# ProPrj_USB_Hub_2026-06-01.net
KiCad netlist of a schematic drawn in EasyEDA Pro
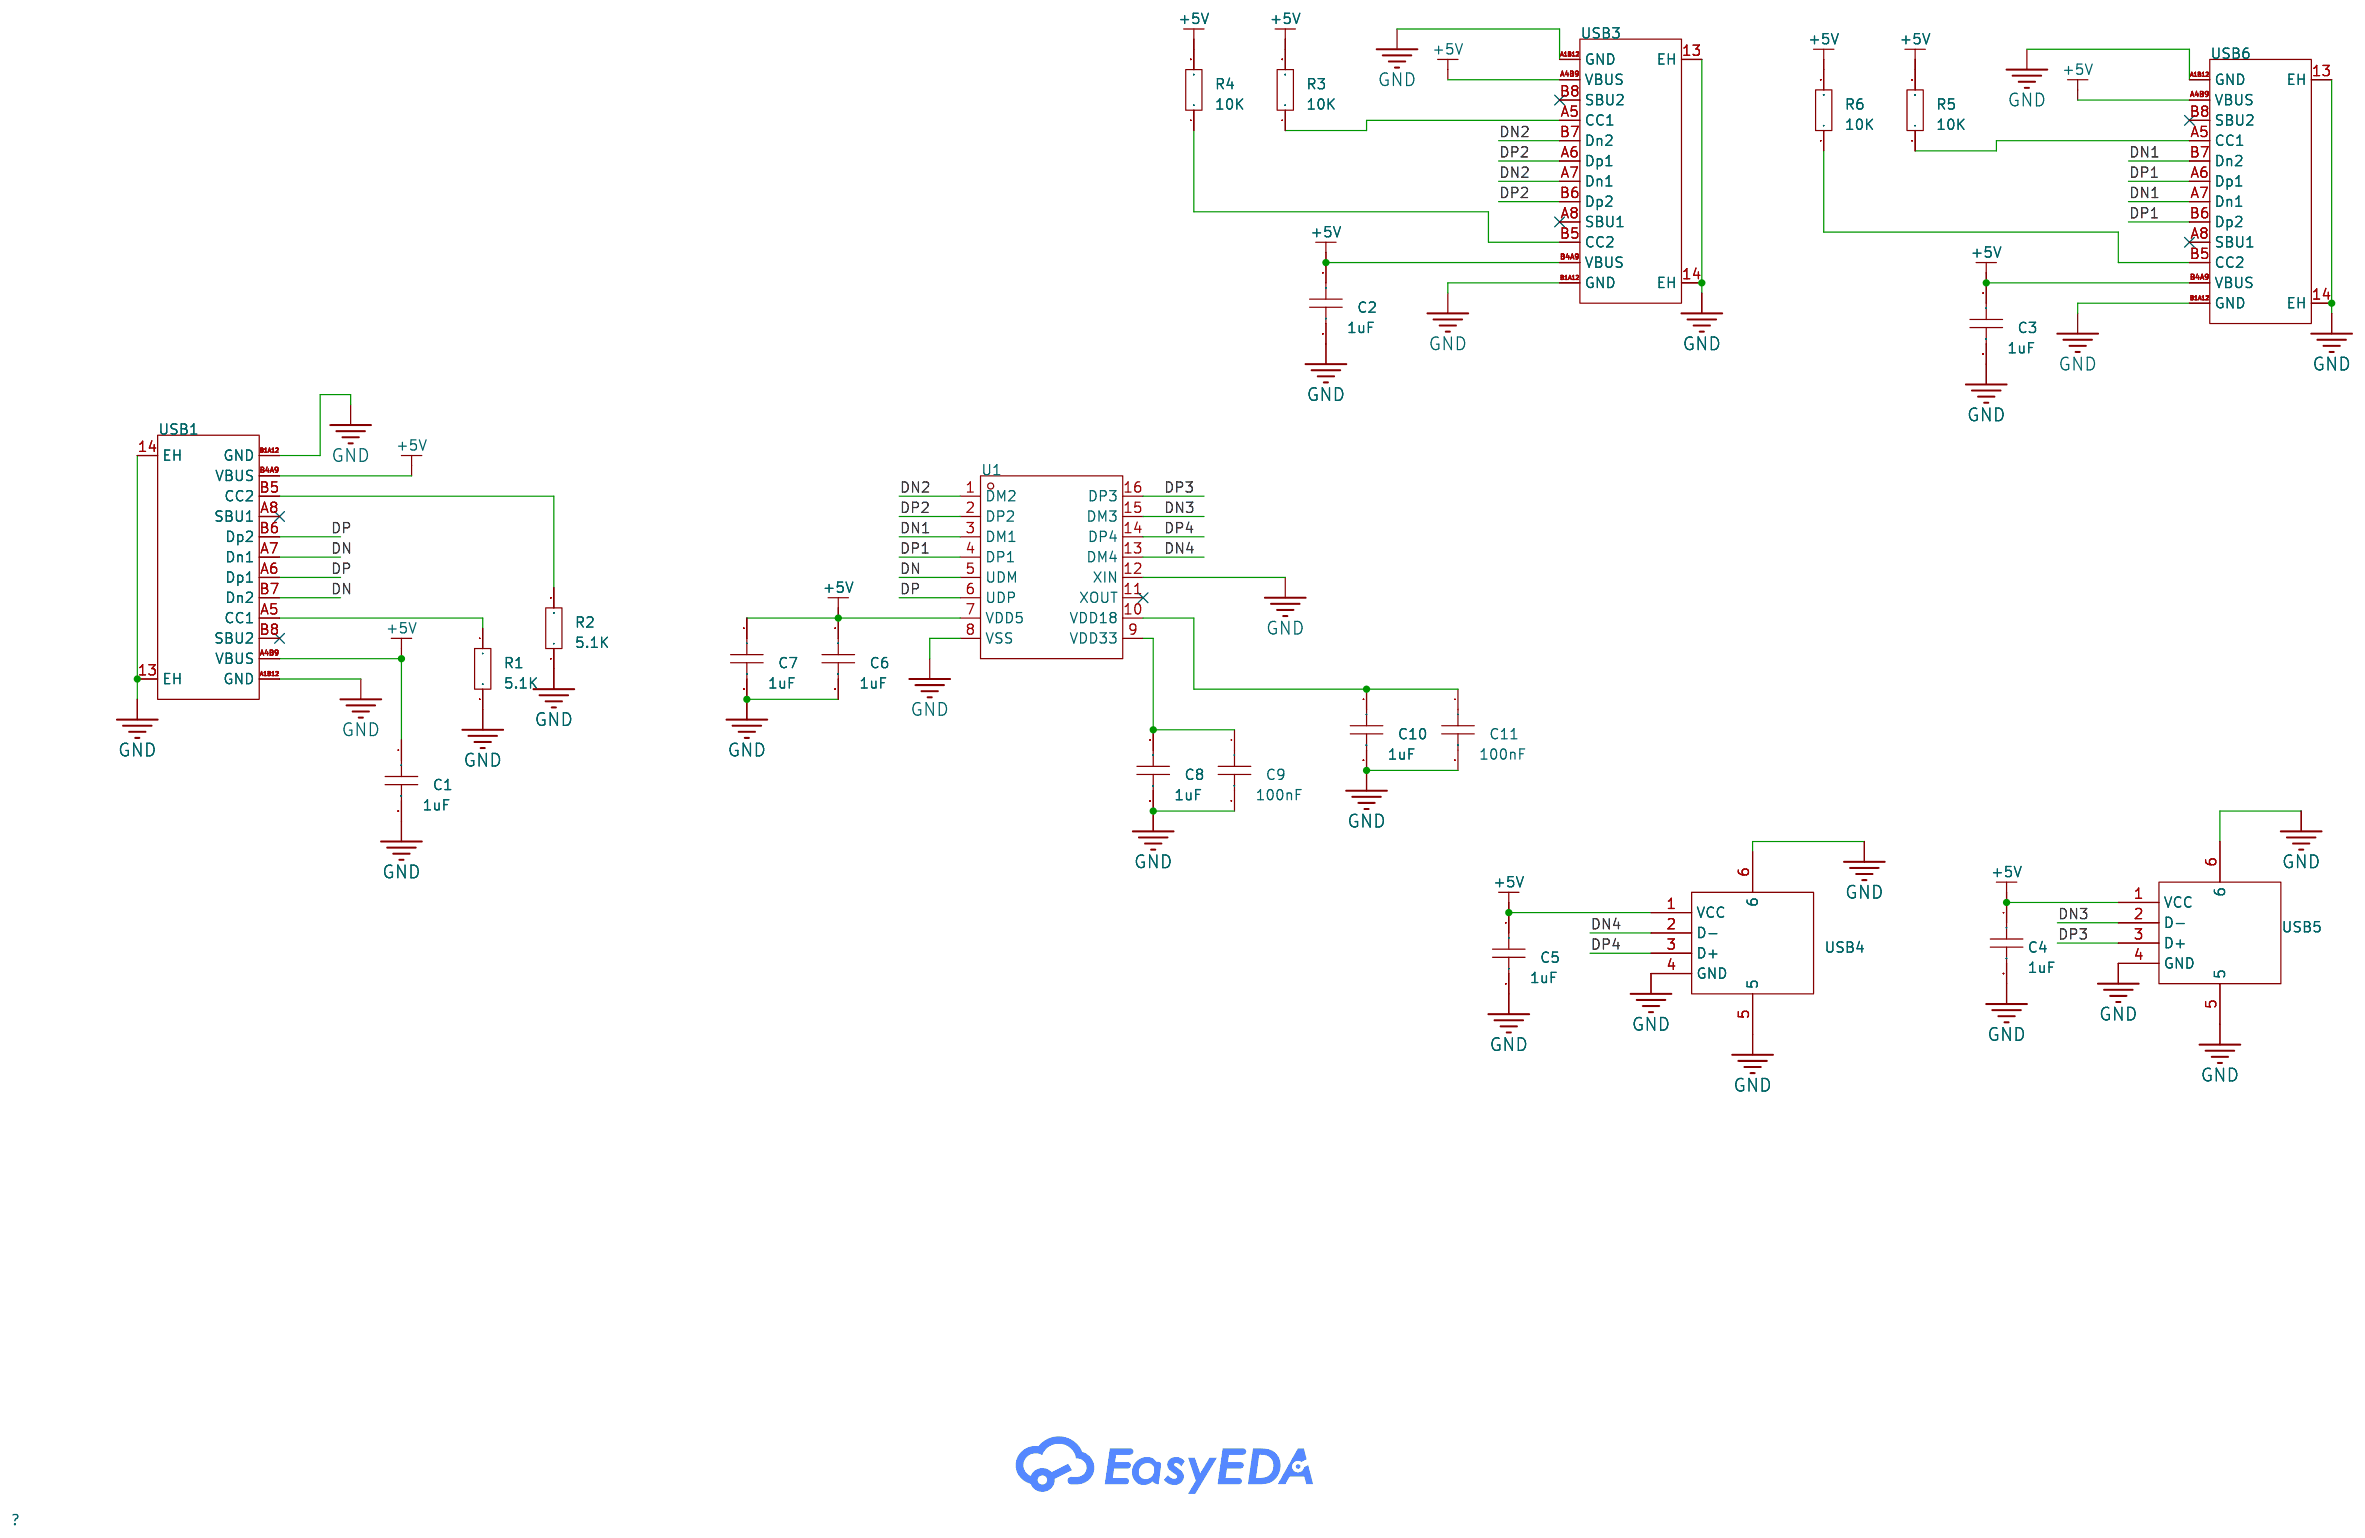
[diagram p0: schematic sheet]

(export (version "E")
  (design (tool "Eeschema 10.0.6"))
  (components
    (comp (ref "C1") (value "1uF") (footprint "easyedapro:C0603") (libsource (lib "easyedapro") (part "CAP")))
    (comp (ref "C2") (value "1uF") (footprint "easyedapro:C0603") (libsource (lib "easyedapro") (part "CAP")))
    (comp (ref "C3") (value "1uF") (footprint "easyedapro:C0603") (libsource (lib "easyedapro") (part "CAP")))
    (comp (ref "C4") (value "1uF") (footprint "easyedapro:C0603") (libsource (lib "easyedapro") (part "CAP")))
    (comp (ref "C5") (value "1uF") (footprint "easyedapro:C0603") (libsource (lib "easyedapro") (part "CAP")))
    (comp (ref "C6") (value "1uF") (footprint "easyedapro:C0603") (libsource (lib "easyedapro") (part "CAP")))
    (comp (ref "C7") (value "1uF") (footprint "easyedapro:C0603") (libsource (lib "easyedapro") (part "CAP")))
    (comp (ref "C8") (value "1uF") (footprint "easyedapro:C0603") (libsource (lib "easyedapro") (part "CAP")))
    (comp (ref "C9")
      (value "100nF")
      (footprint "easyedapro:C0603")
      (libsource (lib "easyedapro") (part "CAP"))
    )
    (comp (ref "C10")
      (value "1uF")
      (footprint "easyedapro:C0603")
      (libsource (lib "easyedapro") (part "CAP"))
    )
    (comp (ref "C11")
      (value "100nF")
      (footprint "easyedapro:C0603")
      (libsource (lib "easyedapro") (part "CAP"))
    )
    (comp (ref "R1")
      (value "5.1K")
      (footprint "easyedapro:R0603")
      (libsource (lib "easyedapro") (part "Res"))
    )
    (comp (ref "R2")
      (value "5.1K")
      (footprint "easyedapro:R0603")
      (libsource (lib "easyedapro") (part "Res"))
    )
    (comp (ref "R3") (value "10K") (footprint "easyedapro:R0603") (libsource (lib "easyedapro") (part "Res")))
    (comp (ref "R4") (value "10K") (footprint "easyedapro:R0603") (libsource (lib "easyedapro") (part "Res")))
    (comp (ref "R5") (value "10K") (footprint "easyedapro:R0603") (libsource (lib "easyedapro") (part "Res")))
    (comp (ref "R6") (value "10K") (footprint "easyedapro:R0603") (libsource (lib "easyedapro") (part "Res")))
    (comp (ref "U1")
      (value "SL2.1s")
      (footprint "easyedapro:SSOP-16_L4.6-W2.6-P0.53-LS4.0-BL")
      (fields (field (name "Manufacturer") "CoreChips(和芯润德)"))
      (libsource (lib "easyedapro") (part "SL2.1S"))
    )
    (comp (ref "USB1")
      (value "TYPE-C 16PIN 2MD(073)")
      (footprint "easyedapro:USB-C-SMD_TYPE-C-16PIN-2MD-073")
      (fields (field (name "Manufacturer") "SHOU HAN(首韩)"))
      (libsource (lib "easyedapro") (part "TYPE-C 16PIN 2MD(073)"))
    )
    (comp (ref "USB3")
      (value "TYPE-C 16PIN 2MD(073)")
      (footprint "easyedapro:USB-C-SMD_TYPE-C-16PIN-2MD-073")
      (fields (field (name "Manufacturer") "SHOU HAN(首韩)"))
      (libsource (lib "easyedapro") (part "TYPE-C 16PIN 2MD(073)"))
    )
    (comp (ref "USB4")
      (value "10.0 QHHTZB6.3")
      (footprint "easyedapro:USB-A-TH_10.0QHHTZB6.3")
      (fields (field (name "Manufacturer") "SHOU HAN(首韩)"))
      (libsource (lib "easyedapro") (part "10.0 QHHTZB6.3"))
    )
    (comp (ref "USB5")
      (value "10.0 QHHTZB6.3")
      (footprint "easyedapro:USB-A-TH_10.0QHHTZB6.3")
      (fields (field (name "Manufacturer") "SHOU HAN(首韩)"))
      (libsource (lib "easyedapro") (part "10.0 QHHTZB6.3"))
    )
    (comp (ref "USB6")
      (value "TYPE-C 16PIN 2MD(073)")
      (footprint "easyedapro:USB-C-SMD_TYPE-C-16PIN-2MD-073")
      (fields (field (name "Manufacturer") "SHOU HAN(首韩)"))
      (libsource (lib "easyedapro") (part "TYPE-C 16PIN 2MD(073)"))
    )
  )
  (nets
    (net (code "1") (name "+5V") (class "Default")
      (node (ref "C1") (pin "1") (pinfunction "1_1") (pintype "input"))
      (node (ref "C2") (pin "1") (pinfunction "1_1") (pintype "input"))
      (node (ref "C3") (pin "1") (pinfunction "1_1") (pintype "input"))
      (node (ref "C4") (pin "1") (pinfunction "1_1") (pintype "input"))
      (node (ref "C5") (pin "1") (pinfunction "1_1") (pintype "input"))
      (node (ref "C6") (pin "1") (pinfunction "1_1") (pintype "input"))
      (node (ref "C7") (pin "1") (pinfunction "1_1") (pintype "input"))
      (node (ref "R3") (pin "2") (pinfunction "2_2") (pintype "input"))
      (node (ref "R4") (pin "2") (pinfunction "2_2") (pintype "input"))
      (node (ref "R5") (pin "2") (pinfunction "2_2") (pintype "input"))
      (node (ref "R6") (pin "2") (pinfunction "2_2") (pintype "input"))
      (node (ref "U1") (pin "7") (pinfunction "VDD5_7") (pintype "unspecified"))
      (node (ref "USB1") (pin "A4B9") (pinfunction "VBUS_A4B9") (pintype "unspecified"))
      (node (ref "USB1") (pin "B4A9") (pinfunction "VBUS_B4A9") (pintype "unspecified"))
      (node (ref "USB3") (pin "A4B9") (pinfunction "VBUS_A4B9") (pintype "unspecified"))
      (node (ref "USB3") (pin "B4A9") (pinfunction "VBUS_B4A9") (pintype "unspecified"))
      (node (ref "USB4") (pin "1") (pinfunction "VCC_1") (pintype "unspecified"))
      (node (ref "USB5") (pin "1") (pinfunction "VCC_1") (pintype "unspecified"))
      (node (ref "USB6") (pin "A4B9") (pinfunction "VBUS_A4B9") (pintype "unspecified"))
      (node (ref "USB6") (pin "B4A9") (pinfunction "VBUS_B4A9") (pintype "unspecified"))
    )
    (net (code "2") (name "/DN") (class "Default")
      (node (ref "U1") (pin "5") (pinfunction "UDM_5") (pintype "unspecified"))
      (node (ref "USB1") (pin "A7") (pinfunction "Dn1_A7") (pintype "unspecified"))
      (node (ref "USB1") (pin "B7") (pinfunction "Dn2_B7") (pintype "unspecified"))
    )
    (net (code "3") (name "/DN1") (class "Default")
      (node (ref "U1") (pin "3") (pinfunction "DM1_3") (pintype "unspecified"))
      (node (ref "USB6") (pin "A7") (pinfunction "Dn1_A7") (pintype "unspecified"))
      (node (ref "USB6") (pin "B7") (pinfunction "Dn2_B7") (pintype "unspecified"))
    )
    (net (code "4") (name "/DN2") (class "Default")
      (node (ref "U1") (pin "1") (pinfunction "DM2_1") (pintype "unspecified"))
      (node (ref "USB3") (pin "A7") (pinfunction "Dn1_A7") (pintype "unspecified"))
      (node (ref "USB3") (pin "B7") (pinfunction "Dn2_B7") (pintype "unspecified"))
    )
    (net (code "5") (name "/DN3") (class "Default")
      (node (ref "U1") (pin "15") (pinfunction "DM3_15") (pintype "unspecified"))
      (node (ref "USB5") (pin "2") (pinfunction "D-_2") (pintype "unspecified"))
    )
    (net (code "6") (name "/DN4") (class "Default")
      (node (ref "U1") (pin "13") (pinfunction "DM4_13") (pintype "unspecified"))
      (node (ref "USB4") (pin "2") (pinfunction "D-_2") (pintype "unspecified"))
    )
    (net (code "7") (name "/DP") (class "Default")
      (node (ref "U1") (pin "6") (pinfunction "UDP_6") (pintype "unspecified"))
      (node (ref "USB1") (pin "A6") (pinfunction "Dp1_A6") (pintype "unspecified"))
      (node (ref "USB1") (pin "B6") (pinfunction "Dp2_B6") (pintype "unspecified"))
    )
    (net (code "8") (name "/DP1") (class "Default")
      (node (ref "U1") (pin "4") (pinfunction "DP1_4") (pintype "unspecified"))
      (node (ref "USB6") (pin "A6") (pinfunction "Dp1_A6") (pintype "unspecified"))
      (node (ref "USB6") (pin "B6") (pinfunction "Dp2_B6") (pintype "unspecified"))
    )
    (net (code "9") (name "/DP2") (class "Default")
      (node (ref "U1") (pin "2") (pinfunction "DP2_2") (pintype "unspecified"))
      (node (ref "USB3") (pin "A6") (pinfunction "Dp1_A6") (pintype "unspecified"))
      (node (ref "USB3") (pin "B6") (pinfunction "Dp2_B6") (pintype "unspecified"))
    )
    (net (code "10") (name "/DP3") (class "Default")
      (node (ref "U1") (pin "16") (pinfunction "DP3_16") (pintype "unspecified"))
      (node (ref "USB5") (pin "3") (pinfunction "D+_3") (pintype "unspecified"))
    )
    (net (code "11") (name "/DP4") (class "Default")
      (node (ref "U1") (pin "14") (pinfunction "DP4_14") (pintype "unspecified"))
      (node (ref "USB4") (pin "3") (pinfunction "D+_3") (pintype "unspecified"))
    )
    (net (code "12") (name "GND") (class "Default")
      (node (ref "C1") (pin "2") (pinfunction "2_2") (pintype "input"))
      (node (ref "C10") (pin "2") (pinfunction "2_2") (pintype "input"))
      (node (ref "C11") (pin "2") (pinfunction "2_2") (pintype "input"))
      (node (ref "C2") (pin "2") (pinfunction "2_2") (pintype "input"))
      (node (ref "C3") (pin "2") (pinfunction "2_2") (pintype "input"))
      (node (ref "C4") (pin "2") (pinfunction "2_2") (pintype "input"))
      (node (ref "C5") (pin "2") (pinfunction "2_2") (pintype "input"))
      (node (ref "C6") (pin "2") (pinfunction "2_2") (pintype "input"))
      (node (ref "C7") (pin "2") (pinfunction "2_2") (pintype "input"))
      (node (ref "C8") (pin "2") (pinfunction "2_2") (pintype "input"))
      (node (ref "C9") (pin "2") (pinfunction "2_2") (pintype "input"))
      (node (ref "R1") (pin "2") (pinfunction "2_2") (pintype "input"))
      (node (ref "R2") (pin "1") (pinfunction "1_1") (pintype "input"))
      (node (ref "U1") (pin "12") (pinfunction "XIN_12") (pintype "unspecified"))
      (node (ref "U1") (pin "8") (pinfunction "VSS_8") (pintype "unspecified"))
      (node (ref "USB1") (pin "13") (pinfunction "EH_13") (pintype "unspecified"))
      (node (ref "USB1") (pin "14") (pinfunction "EH_14") (pintype "unspecified"))
      (node (ref "USB1") (pin "A1B12") (pinfunction "GND_A1B12") (pintype "unspecified"))
      (node (ref "USB1") (pin "B1A12") (pinfunction "GND_B1A12") (pintype "unspecified"))
      (node (ref "USB3") (pin "13") (pinfunction "EH_13") (pintype "unspecified"))
      (node (ref "USB3") (pin "14") (pinfunction "EH_14") (pintype "unspecified"))
      (node (ref "USB3") (pin "A1B12") (pinfunction "GND_A1B12") (pintype "unspecified"))
      (node (ref "USB3") (pin "B1A12") (pinfunction "GND_B1A12") (pintype "unspecified"))
      (node (ref "USB4") (pin "4") (pinfunction "GND_4") (pintype "unspecified"))
      (node (ref "USB4") (pin "5") (pinfunction "5_5") (pintype "unspecified"))
      (node (ref "USB4") (pin "6") (pinfunction "6_6") (pintype "unspecified"))
      (node (ref "USB5") (pin "4") (pinfunction "GND_4") (pintype "unspecified"))
      (node (ref "USB5") (pin "5") (pinfunction "5_5") (pintype "unspecified"))
      (node (ref "USB5") (pin "6") (pinfunction "6_6") (pintype "unspecified"))
      (node (ref "USB6") (pin "13") (pinfunction "EH_13") (pintype "unspecified"))
      (node (ref "USB6") (pin "14") (pinfunction "EH_14") (pintype "unspecified"))
      (node (ref "USB6") (pin "A1B12") (pinfunction "GND_A1B12") (pintype "unspecified"))
      (node (ref "USB6") (pin "B1A12") (pinfunction "GND_B1A12") (pintype "unspecified"))
    )
    (net (code "13") (name "Net-(U1-VDD18)") (class "Default")
      (node (ref "C10") (pin "1") (pinfunction "1_1") (pintype "input"))
      (node (ref "C11") (pin "1") (pinfunction "1_1") (pintype "input"))
      (node (ref "U1") (pin "10") (pinfunction "VDD18_10") (pintype "unspecified"))
    )
    (net (code "14") (name "Net-(U1-VDD33)") (class "Default")
      (node (ref "C8") (pin "1") (pinfunction "1_1") (pintype "input"))
      (node (ref "C9") (pin "1") (pinfunction "1_1") (pintype "input"))
      (node (ref "U1") (pin "9") (pinfunction "VDD33_9") (pintype "unspecified"))
    )
    (net (code "15") (name "Net-(USB1-CC1)") (class "Default")
      (node (ref "R1") (pin "1") (pinfunction "1_1") (pintype "input"))
      (node (ref "USB1") (pin "A5") (pinfunction "CC1_A5") (pintype "unspecified"))
    )
    (net (code "16") (name "Net-(USB1-CC2)") (class "Default")
      (node (ref "R2") (pin "2") (pinfunction "2_2") (pintype "input"))
      (node (ref "USB1") (pin "B5") (pinfunction "CC2_B5") (pintype "unspecified"))
    )
    (net (code "17") (name "Net-(USB3-CC1)") (class "Default")
      (node (ref "R3") (pin "1") (pinfunction "1_1") (pintype "input"))
      (node (ref "USB3") (pin "A5") (pinfunction "CC1_A5") (pintype "unspecified"))
    )
    (net (code "18") (name "Net-(USB3-CC2)") (class "Default")
      (node (ref "R4") (pin "1") (pinfunction "1_1") (pintype "input"))
      (node (ref "USB3") (pin "B5") (pinfunction "CC2_B5") (pintype "unspecified"))
    )
    (net (code "19") (name "Net-(USB6-CC1)") (class "Default")
      (node (ref "R5") (pin "1") (pinfunction "1_1") (pintype "input"))
      (node (ref "USB6") (pin "A5") (pinfunction "CC1_A5") (pintype "unspecified"))
    )
    (net (code "20") (name "Net-(USB6-CC2)") (class "Default")
      (node (ref "R6") (pin "1") (pinfunction "1_1") (pintype "input"))
      (node (ref "USB6") (pin "B5") (pinfunction "CC2_B5") (pintype "unspecified"))
    )
    (net (code "21") (name "unconnected-(U1-XOUT-Pad11)") (class "Default")
      (node (ref "U1") (pin "11") (pinfunction "XOUT_11") (pintype "unspecified+no_connect"))
    )
    (net (code "22") (name "unconnected-(USB1-SBU1-PadA8)") (class "Default")
      (node (ref "USB1") (pin "A8") (pinfunction "SBU1_A8") (pintype "unspecified+no_connect"))
    )
    (net (code "23") (name "unconnected-(USB1-SBU2-PadB8)") (class "Default")
      (node (ref "USB1") (pin "B8") (pinfunction "SBU2_B8") (pintype "unspecified+no_connect"))
    )
    (net (code "24") (name "unconnected-(USB3-SBU1-PadA8)") (class "Default")
      (node (ref "USB3") (pin "A8") (pinfunction "SBU1_A8") (pintype "unspecified+no_connect"))
    )
    (net (code "25") (name "unconnected-(USB3-SBU2-PadB8)") (class "Default")
      (node (ref "USB3") (pin "B8") (pinfunction "SBU2_B8") (pintype "unspecified+no_connect"))
    )
    (net (code "26") (name "unconnected-(USB6-SBU1-PadA8)") (class "Default")
      (node (ref "USB6") (pin "A8") (pinfunction "SBU1_A8") (pintype "unspecified+no_connect"))
    )
    (net (code "27") (name "unconnected-(USB6-SBU2-PadB8)") (class "Default")
      (node (ref "USB6") (pin "B8") (pinfunction "SBU2_B8") (pintype "unspecified+no_connect"))
    )
  )
)
